# arduino_board.net
KiCad netlist of a schematic drawn in EAGLE
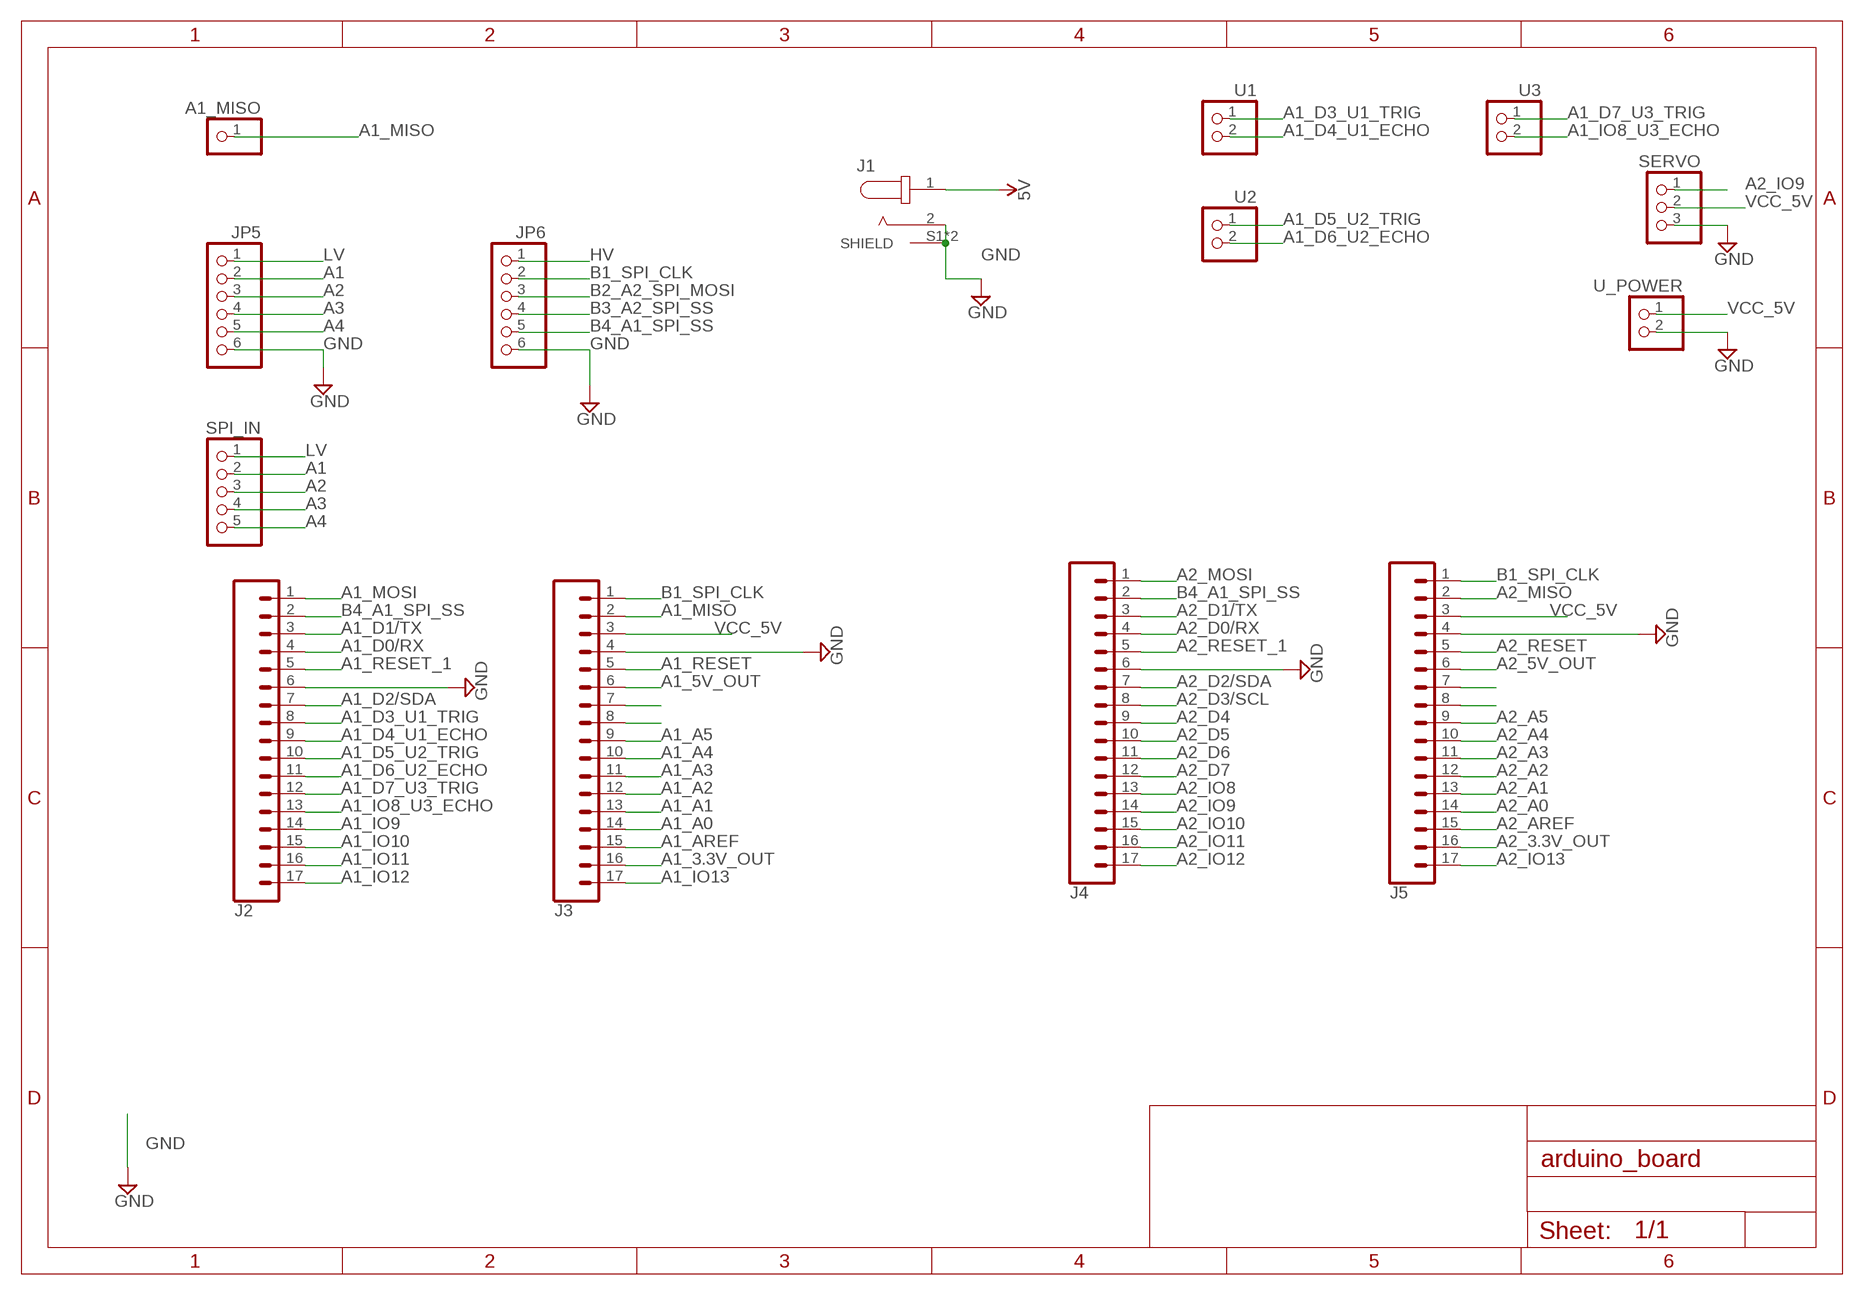
[diagram p0: schematic, sheet 1]

(export (version "E")
  (design (tool "Eeschema 10.0.6"))
  (components
    (comp (ref "A1_MISO")
      (value "PINHD-1X1")
      (footprint "eagle-import:1X01")
      (libsource (lib "eagle-import") (part "PINHD-1X1"))
    )
    (comp (ref "J1")
      (value "PJ-063AH")
      (footprint "eagle-import:CUI_PJ-063AH")
      (fields (field (name "MF") "CUI Inc."))
      (libsource (lib "eagle-import") (part "PJ-063AH"))
    )
    (comp (ref "J2")
      (value "CONN_17")
      (footprint "eagle-import:1X17")
      (libsource (lib "eagle-import") (part "CONN_17"))
    )
    (comp (ref "J3")
      (value "CONN_17")
      (footprint "eagle-import:1X17")
      (libsource (lib "eagle-import") (part "CONN_17"))
    )
    (comp (ref "J4")
      (value "CONN_17")
      (footprint "eagle-import:1X17")
      (libsource (lib "eagle-import") (part "CONN_17"))
    )
    (comp (ref "J5")
      (value "CONN_17")
      (footprint "eagle-import:1X17")
      (libsource (lib "eagle-import") (part "CONN_17"))
    )
    (comp (ref "JP5")
      (value "PINHD-1X6")
      (footprint "eagle-import:1X06")
      (libsource (lib "eagle-import") (part "PINHD-1X6"))
    )
    (comp (ref "JP6")
      (value "PINHD-1X6")
      (footprint "eagle-import:1X06")
      (libsource (lib "eagle-import") (part "PINHD-1X6"))
    )
    (comp (ref "SERVO")
      (value "PINHD-1X3")
      (footprint "eagle-import:1X03")
      (libsource (lib "eagle-import") (part "PINHD-1X3"))
    )
    (comp (ref "SPI_IN")
      (value "PINHD-1X5")
      (footprint "eagle-import:1X05")
      (libsource (lib "eagle-import") (part "PINHD-1X5"))
    )
    (comp (ref "U1")
      (value "PINHD-1X2")
      (footprint "eagle-import:1X02")
      (libsource (lib "eagle-import") (part "PINHD-1X2"))
    )
    (comp (ref "U2")
      (value "PINHD-1X2")
      (footprint "eagle-import:1X02")
      (libsource (lib "eagle-import") (part "PINHD-1X2"))
    )
    (comp (ref "U3")
      (value "PINHD-1X2")
      (footprint "eagle-import:1X02")
      (libsource (lib "eagle-import") (part "PINHD-1X2"))
    )
    (comp (ref "U_POWER")
      (value "PINHD-1X2")
      (footprint "eagle-import:1X02")
      (libsource (lib "eagle-import") (part "PINHD-1X2"))
    )
  )
  (nets
    (net (code "1") (name "/A1") (class "Default")
      (node (ref "JP5") (pin "2") (pinfunction "2_2") (pintype "passive"))
      (node (ref "SPI_IN") (pin "2") (pinfunction "2_2") (pintype "passive"))
    )
    (net (code "2") (name "/A1_3.3V_OUT") (class "Default")
      (node (ref "J3") (pin "16") (pinfunction "16_16") (pintype "passive"))
    )
    (net (code "3") (name "/A1_5V_OUT") (class "Default")
      (node (ref "J3") (pin "6") (pinfunction "6_6") (pintype "passive"))
    )
    (net (code "4") (name "/A1_A0") (class "Default")
      (node (ref "J3") (pin "14") (pinfunction "14_14") (pintype "passive"))
    )
    (net (code "5") (name "/A1_A1") (class "Default")
      (node (ref "J3") (pin "13") (pinfunction "13_13") (pintype "passive"))
    )
    (net (code "6") (name "/A1_A2") (class "Default")
      (node (ref "J3") (pin "12") (pinfunction "12_12") (pintype "passive"))
    )
    (net (code "7") (name "/A1_A3") (class "Default")
      (node (ref "J3") (pin "11") (pinfunction "11_11") (pintype "passive"))
    )
    (net (code "8") (name "/A1_A4") (class "Default")
      (node (ref "J3") (pin "10") (pinfunction "10_10") (pintype "passive"))
    )
    (net (code "9") (name "/A1_A5") (class "Default")
      (node (ref "J3") (pin "9") (pinfunction "9_9") (pintype "passive"))
    )
    (net (code "10") (name "/A1_AREF") (class "Default")
      (node (ref "J3") (pin "15") (pinfunction "15_15") (pintype "passive"))
    )
    (net (code "11") (name "/A1_D0{slash}RX") (class "Default")
      (node (ref "J2") (pin "4") (pinfunction "4_4") (pintype "passive"))
    )
    (net (code "12") (name "/A1_D1{slash}TX") (class "Default")
      (node (ref "J2") (pin "3") (pinfunction "3_3") (pintype "passive"))
    )
    (net (code "13") (name "/A1_D2{slash}SDA") (class "Default")
      (node (ref "J2") (pin "7") (pinfunction "7_7") (pintype "passive"))
    )
    (net (code "14") (name "/A1_D3_U1_TRIG") (class "Default")
      (node (ref "J2") (pin "8") (pinfunction "8_8") (pintype "passive"))
      (node (ref "U1") (pin "1") (pinfunction "1_1") (pintype "passive"))
    )
    (net (code "15") (name "/A1_D4_U1_ECHO") (class "Default")
      (node (ref "J2") (pin "9") (pinfunction "9_9") (pintype "passive"))
      (node (ref "U1") (pin "2") (pinfunction "2_2") (pintype "passive"))
    )
    (net (code "16") (name "/A1_D5_U2_TRIG") (class "Default")
      (node (ref "J2") (pin "10") (pinfunction "10_10") (pintype "passive"))
      (node (ref "U2") (pin "1") (pinfunction "1_1") (pintype "passive"))
    )
    (net (code "17") (name "/A1_D6_U2_ECHO") (class "Default")
      (node (ref "J2") (pin "11") (pinfunction "11_11") (pintype "passive"))
      (node (ref "U2") (pin "2") (pinfunction "2_2") (pintype "passive"))
    )
    (net (code "18") (name "/A1_D7_U3_TRIG") (class "Default")
      (node (ref "J2") (pin "12") (pinfunction "12_12") (pintype "passive"))
      (node (ref "U3") (pin "1") (pinfunction "1_1") (pintype "passive"))
    )
    (net (code "19") (name "/A1_IO8_U3_ECHO") (class "Default")
      (node (ref "J2") (pin "13") (pinfunction "13_13") (pintype "passive"))
      (node (ref "U3") (pin "2") (pinfunction "2_2") (pintype "passive"))
    )
    (net (code "20") (name "/A1_IO9") (class "Default")
      (node (ref "J2") (pin "14") (pinfunction "14_14") (pintype "passive"))
    )
    (net (code "21") (name "/A1_IO10") (class "Default")
      (node (ref "J2") (pin "15") (pinfunction "15_15") (pintype "passive"))
    )
    (net (code "22") (name "/A1_IO11") (class "Default")
      (node (ref "J2") (pin "16") (pinfunction "16_16") (pintype "passive"))
    )
    (net (code "23") (name "/A1_IO12") (class "Default")
      (node (ref "J2") (pin "17") (pinfunction "17_17") (pintype "passive"))
    )
    (net (code "24") (name "/A1_IO13") (class "Default")
      (node (ref "J3") (pin "17") (pinfunction "17_17") (pintype "passive"))
    )
    (net (code "25") (name "/A1_MISO") (class "Default")
      (node (ref "A1_MISO") (pin "1") (pinfunction "1_1") (pintype "passive"))
      (node (ref "J3") (pin "2") (pinfunction "2_2") (pintype "passive"))
    )
    (net (code "26") (name "/A1_MOSI") (class "Default")
      (node (ref "J2") (pin "1") (pinfunction "1_1") (pintype "passive"))
    )
    (net (code "27") (name "/A1_RESET") (class "Default")
      (node (ref "J3") (pin "5") (pinfunction "5_5") (pintype "passive"))
    )
    (net (code "28") (name "/A1_RESET_1") (class "Default")
      (node (ref "J2") (pin "5") (pinfunction "5_5") (pintype "passive"))
    )
    (net (code "29") (name "/A2") (class "Default")
      (node (ref "JP5") (pin "3") (pinfunction "3_3") (pintype "passive"))
      (node (ref "SPI_IN") (pin "3") (pinfunction "3_3") (pintype "passive"))
    )
    (net (code "30") (name "/A2_3.3V_OUT") (class "Default")
      (node (ref "J5") (pin "16") (pinfunction "16_16") (pintype "passive"))
    )
    (net (code "31") (name "/A2_5V_OUT") (class "Default")
      (node (ref "J5") (pin "6") (pinfunction "6_6") (pintype "passive"))
    )
    (net (code "32") (name "/A2_A0") (class "Default")
      (node (ref "J5") (pin "14") (pinfunction "14_14") (pintype "passive"))
    )
    (net (code "33") (name "/A2_A1") (class "Default")
      (node (ref "J5") (pin "13") (pinfunction "13_13") (pintype "passive"))
    )
    (net (code "34") (name "/A2_A2") (class "Default")
      (node (ref "J5") (pin "12") (pinfunction "12_12") (pintype "passive"))
    )
    (net (code "35") (name "/A2_A3") (class "Default")
      (node (ref "J5") (pin "11") (pinfunction "11_11") (pintype "passive"))
    )
    (net (code "36") (name "/A2_A4") (class "Default")
      (node (ref "J5") (pin "10") (pinfunction "10_10") (pintype "passive"))
    )
    (net (code "37") (name "/A2_A5") (class "Default")
      (node (ref "J5") (pin "9") (pinfunction "9_9") (pintype "passive"))
    )
    (net (code "38") (name "/A2_AREF") (class "Default")
      (node (ref "J5") (pin "15") (pinfunction "15_15") (pintype "passive"))
    )
    (net (code "39") (name "/A2_D0{slash}RX") (class "Default")
      (node (ref "J4") (pin "4") (pinfunction "4_4") (pintype "passive"))
    )
    (net (code "40") (name "/A2_D1{slash}TX") (class "Default")
      (node (ref "J4") (pin "3") (pinfunction "3_3") (pintype "passive"))
    )
    (net (code "41") (name "/A2_D2{slash}SDA") (class "Default")
      (node (ref "J4") (pin "7") (pinfunction "7_7") (pintype "passive"))
    )
    (net (code "42") (name "/A2_D3{slash}SCL") (class "Default")
      (node (ref "J4") (pin "8") (pinfunction "8_8") (pintype "passive"))
    )
    (net (code "43") (name "/A2_D4") (class "Default")
      (node (ref "J4") (pin "9") (pinfunction "9_9") (pintype "passive"))
    )
    (net (code "44") (name "/A2_D5") (class "Default")
      (node (ref "J4") (pin "10") (pinfunction "10_10") (pintype "passive"))
    )
    (net (code "45") (name "/A2_D6") (class "Default")
      (node (ref "J4") (pin "11") (pinfunction "11_11") (pintype "passive"))
    )
    (net (code "46") (name "/A2_D7") (class "Default")
      (node (ref "J4") (pin "12") (pinfunction "12_12") (pintype "passive"))
    )
    (net (code "47") (name "/A2_IO8") (class "Default")
      (node (ref "J4") (pin "13") (pinfunction "13_13") (pintype "passive"))
    )
    (net (code "48") (name "/A2_IO9") (class "Default")
      (node (ref "J4") (pin "14") (pinfunction "14_14") (pintype "passive"))
      (node (ref "SERVO") (pin "1") (pinfunction "1_1") (pintype "passive"))
    )
    (net (code "49") (name "/A2_IO10") (class "Default")
      (node (ref "J4") (pin "15") (pinfunction "15_15") (pintype "passive"))
    )
    (net (code "50") (name "/A2_IO11") (class "Default")
      (node (ref "J4") (pin "16") (pinfunction "16_16") (pintype "passive"))
    )
    (net (code "51") (name "/A2_IO12") (class "Default")
      (node (ref "J4") (pin "17") (pinfunction "17_17") (pintype "passive"))
    )
    (net (code "52") (name "/A2_IO13") (class "Default")
      (node (ref "J5") (pin "17") (pinfunction "17_17") (pintype "passive"))
    )
    (net (code "53") (name "/A2_MISO") (class "Default")
      (node (ref "J5") (pin "2") (pinfunction "2_2") (pintype "passive"))
    )
    (net (code "54") (name "/A2_MOSI") (class "Default")
      (node (ref "J4") (pin "1") (pinfunction "1_1") (pintype "passive"))
    )
    (net (code "55") (name "/A2_RESET") (class "Default")
      (node (ref "J5") (pin "5") (pinfunction "5_5") (pintype "passive"))
    )
    (net (code "56") (name "/A2_RESET_1") (class "Default")
      (node (ref "J4") (pin "5") (pinfunction "5_5") (pintype "passive"))
    )
    (net (code "57") (name "/A3") (class "Default")
      (node (ref "JP5") (pin "4") (pinfunction "4_4") (pintype "passive"))
      (node (ref "SPI_IN") (pin "4") (pinfunction "4_4") (pintype "passive"))
    )
    (net (code "58") (name "/A4") (class "Default")
      (node (ref "JP5") (pin "5") (pinfunction "5_5") (pintype "passive"))
      (node (ref "SPI_IN") (pin "5") (pinfunction "5_5") (pintype "passive"))
    )
    (net (code "59") (name "/B1_SPI_CLK") (class "Default")
      (node (ref "J3") (pin "1") (pinfunction "1_1") (pintype "passive"))
      (node (ref "J5") (pin "1") (pinfunction "1_1") (pintype "passive"))
      (node (ref "JP6") (pin "2") (pinfunction "2_2") (pintype "passive"))
    )
    (net (code "60") (name "/B2_A2_SPI_MOSI") (class "Default")
      (node (ref "JP6") (pin "3") (pinfunction "3_3") (pintype "passive"))
    )
    (net (code "61") (name "/B3_A2_SPI_SS") (class "Default")
      (node (ref "JP6") (pin "4") (pinfunction "4_4") (pintype "passive"))
    )
    (net (code "62") (name "/B4_A1_SPI_SS") (class "Default")
      (node (ref "J2") (pin "2") (pinfunction "2_2") (pintype "passive"))
      (node (ref "J4") (pin "2") (pinfunction "2_2") (pintype "passive"))
      (node (ref "JP6") (pin "5") (pinfunction "5_5") (pintype "passive"))
    )
    (net (code "63") (name "/HV") (class "Default")
      (node (ref "JP6") (pin "1") (pinfunction "1_1") (pintype "passive"))
    )
    (net (code "64") (name "/LV") (class "Default")
      (node (ref "JP5") (pin "1") (pinfunction "1_1") (pintype "passive"))
      (node (ref "SPI_IN") (pin "1") (pinfunction "1_1") (pintype "passive"))
    )
    (net (code "65") (name "/VCC_5V") (class "Default")
      (node (ref "J3") (pin "3") (pinfunction "3_3") (pintype "passive"))
      (node (ref "J5") (pin "3") (pinfunction "3_3") (pintype "passive"))
      (node (ref "SERVO") (pin "2") (pinfunction "2_2") (pintype "passive"))
      (node (ref "U_POWER") (pin "1") (pinfunction "1_1") (pintype "passive"))
    )
    (net (code "66") (name "5V") (class "Default")
      (node (ref "J1") (pin "1") (pinfunction "1_1") (pintype "passive"))
    )
    (net (code "67") (name "GND") (class "Default")
      (node (ref "J1") (pin "2") (pinfunction "2_2") (pintype "passive"))
      (node (ref "J1") (pin "S1") (pinfunction "SHIELD_S1") (pintype "power_in"))
      (node (ref "J1") (pin "S2") (pinfunction "SHIELD_S2") (pintype "power_in"))
      (node (ref "J2") (pin "6") (pinfunction "6_6") (pintype "passive"))
      (node (ref "J3") (pin "4") (pinfunction "4_4") (pintype "passive"))
      (node (ref "J4") (pin "6") (pinfunction "6_6") (pintype "passive"))
      (node (ref "J5") (pin "4") (pinfunction "4_4") (pintype "passive"))
      (node (ref "JP5") (pin "6") (pinfunction "6_6") (pintype "passive"))
      (node (ref "JP6") (pin "6") (pinfunction "6_6") (pintype "passive"))
      (node (ref "SERVO") (pin "3") (pinfunction "3_3") (pintype "passive"))
      (node (ref "U_POWER") (pin "2") (pinfunction "2_2") (pintype "passive"))
    )
    (net (code "68") (name "unconnected-(J3-Pad7)") (class "Default")
      (node (ref "J3") (pin "7") (pinfunction "7_7") (pintype "passive"))
    )
    (net (code "69") (name "unconnected-(J3-Pad8)") (class "Default")
      (node (ref "J3") (pin "8") (pinfunction "8_8") (pintype "passive"))
    )
    (net (code "70") (name "unconnected-(J5-Pad7)") (class "Default")
      (node (ref "J5") (pin "7") (pinfunction "7_7") (pintype "passive"))
    )
    (net (code "71") (name "unconnected-(J5-Pad8)") (class "Default")
      (node (ref "J5") (pin "8") (pinfunction "8_8") (pintype "passive"))
    )
  )
)
